# ESP8266-Thing-Dev.net
KiCad netlist of a schematic drawn in EAGLE
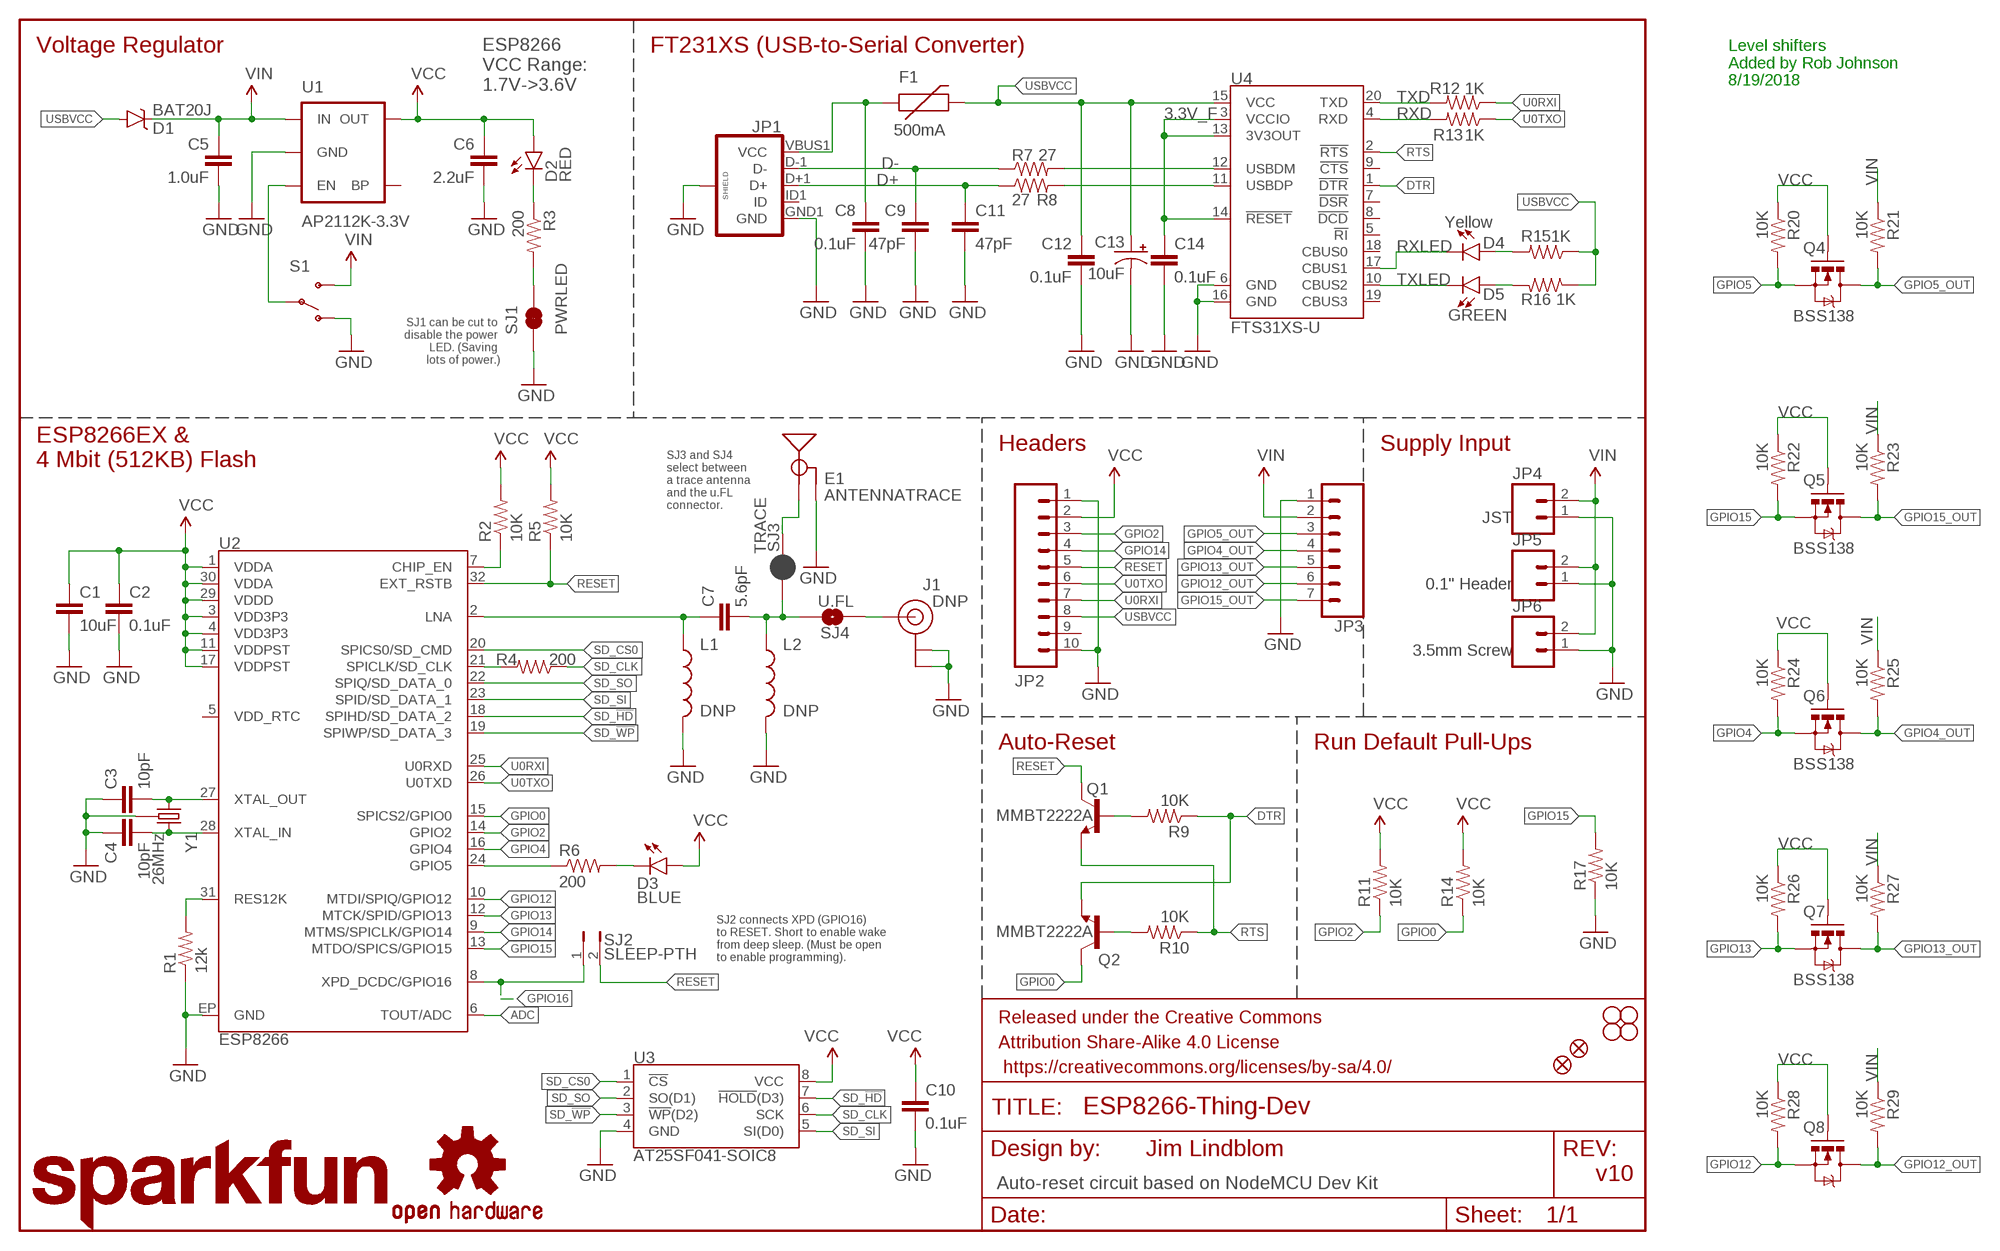
[diagram p0: schematic, sheet 1]

(export (version "E")
  (design (tool "Eeschema 10.0.6"))
  (components
    (comp (ref "C1")
      (value "10uF")
      (footprint "eagle-import:0603-CAP")
      (libsource (lib "eagle-import") (part "10UF-6.3V-20%(0603)"))
    )
    (comp (ref "C2")
      (value "0.1uF")
      (footprint "eagle-import:0603-CAP")
      (libsource (lib "eagle-import") (part "0.1UF-25V(+80/-20%)(0603)"))
    )
    (comp (ref "C3")
      (value "10pF")
      (footprint "eagle-import:0603-CAP")
      (libsource (lib "eagle-import") (part "10PF-50V-5%(0603)"))
    )
    (comp (ref "C4")
      (value "10pF")
      (footprint "eagle-import:0603-CAP")
      (libsource (lib "eagle-import") (part "10PF-50V-5%(0603)"))
    )
    (comp (ref "C5")
      (value "1.0uF")
      (footprint "eagle-import:0805")
      (libsource (lib "eagle-import") (part "1.0UF-25V-+80/-20(0805)"))
    )
    (comp (ref "C6")
      (value "2.2uF")
      (footprint "eagle-import:0603-CAP")
      (libsource (lib "eagle-import") (part "2.2UF-10V-20%(0603)"))
    )
    (comp (ref "C7")
      (value "5.6pF")
      (footprint "eagle-import:0603-CAP")
      (libsource (lib "eagle-import") (part "CAP0603-CAP"))
    )
    (comp (ref "C8")
      (value "0.1uF")
      (footprint "eagle-import:0603-CAP")
      (libsource (lib "eagle-import") (part "0.1UF-25V(+80/-20%)(0603)"))
    )
    (comp (ref "C9")
      (value "47pF")
      (footprint "eagle-import:0603-CAP")
      (libsource (lib "eagle-import") (part "47PF-50V-5%(0603)"))
    )
    (comp (ref "C10")
      (value "0.1uF")
      (footprint "eagle-import:0603-CAP")
      (libsource (lib "eagle-import") (part "0.1UF-25V(+80/-20%)(0603)"))
    )
    (comp (ref "C11")
      (value "47pF")
      (footprint "eagle-import:0603-CAP")
      (libsource (lib "eagle-import") (part "47PF-50V-5%(0603)"))
    )
    (comp (ref "C12")
      (value "0.1uF")
      (footprint "eagle-import:0603-CAP")
      (libsource (lib "eagle-import") (part "0.1UF-25V(+80/-20%)(0603)"))
    )
    (comp (ref "C13")
      (value "10uF")
      (footprint "eagle-import:EIA3216")
      (libsource (lib "eagle-import") (part "10UF-16V-10%(TANT)"))
    )
    (comp (ref "C14")
      (value "0.1uF")
      (footprint "eagle-import:0603-CAP")
      (libsource (lib "eagle-import") (part "0.1UF-25V(+80/-20%)(0603)"))
    )
    (comp (ref "D1")
      (value "BAT20J")
      (footprint "eagle-import:SOD-323")
      (libsource (lib "eagle-import") (part "DIODE-SCHOTTKY-BAT20J"))
    )
    (comp (ref "D2")
      (value "RED")
      (footprint "eagle-import:LED-0603")
      (libsource (lib "eagle-import") (part "LED-RED0603"))
    )
    (comp (ref "D3")
      (value "BLUE")
      (footprint "eagle-import:LED-0603")
      (libsource (lib "eagle-import") (part "LED-BLUE0603"))
    )
    (comp (ref "D4")
      (value "Yellow")
      (footprint "eagle-import:LED-0603")
      (libsource (lib "eagle-import") (part "LED-YELLOW0603"))
    )
    (comp (ref "D5")
      (value "GREEN")
      (footprint "eagle-import:LED-0603")
      (libsource (lib "eagle-import") (part "LED-GREEN0603"))
    )
    (comp (ref "E1")
      (value "ANTENNATRACE")
      (footprint "eagle-import:TRACE_ANTENNA_2.4GHZ_25.7MM")
      (libsource (lib "eagle-import") (part "ANTENNATRACE"))
    )
    (comp (ref "F1")
      (value "500mA")
      (footprint "eagle-import:PTC-1206")
      (libsource (lib "eagle-import") (part "PTCSMD"))
    )
    (comp (ref "FID1")
      (value "FIDUCIAL1X2")
      (footprint "eagle-import:FIDUCIAL-1X2")
      (libsource (lib "eagle-import") (part "FIDUCIAL1X2"))
    )
    (comp (ref "FID2")
      (value "FIDUCIAL1X2")
      (footprint "eagle-import:FIDUCIAL-1X2")
      (libsource (lib "eagle-import") (part "FIDUCIAL1X2"))
    )
    (comp (ref "FRAME1")
      (value "FRAME-LETTER")
      (footprint "eagle-import:CREATIVE_COMMONS")
      (libsource (lib "eagle-import") (part "FRAME-LETTER"))
    )
    (comp (ref "J1")
      (value "DNP")
      (footprint "eagle-import:U.FL")
      (libsource (lib "eagle-import") (part "U.FL"))
    )
    (comp (ref "JP1")
      (value "USB_MICROB_PLUGCONN-11752")
      (footprint "eagle-import:USB-B-MICRO-SMD_V03")
      (libsource (lib "eagle-import") (part "USB_MICROB_PLUGCONN-11752"))
    )
    (comp (ref "JP2")
      (value "M10NO_SILK_PTH_FEMALE")
      (footprint "eagle-import:1X10_NO_SILK")
      (libsource (lib "eagle-import") (part "M10NO_SILK_PTH_FEMALE"))
    )
    (comp (ref "JP3")
      (value "CONN_07NO_SILK")
      (footprint "eagle-import:1X07_NO_SILK")
      (libsource (lib "eagle-import") (part "CONN_07NO_SILK"))
    )
    (comp (ref "JP4")
      (value "M02JST-PTH-2")
      (footprint "eagle-import:JST-2-PTH")
      (libsource (lib "eagle-import") (part "M02JST-PTH-2"))
    )
    (comp (ref "JP5")
      (value "M021X02_NO_SILK")
      (footprint "eagle-import:1X02_NO_SILK")
      (libsource (lib "eagle-import") (part "M021X02_NO_SILK"))
    )
    (comp (ref "JP6")
      (value "M023.5MM-NO_SILK")
      (footprint "eagle-import:SCREWTERMINAL-3.5MM-2-NS")
      (libsource (lib "eagle-import") (part "M023.5MM-NO_SILK"))
    )
    (comp (ref "L1")
      (value "DNP")
      (footprint "eagle-import:0603")
      (libsource (lib "eagle-import") (part "INDUCTOR0603"))
    )
    (comp (ref "L2")
      (value "DNP")
      (footprint "eagle-import:0603")
      (libsource (lib "eagle-import") (part "INDUCTOR0603"))
    )
    (comp (ref "LOGO1")
      (value "SFE_LOGO_NAME.2_INCH")
      (footprint "eagle-import:SFE_LOGO_NAME_.2")
      (libsource (lib "eagle-import") (part "SFE_LOGO_NAME.2_INCH"))
    )
    (comp (ref "LOGO2")
      (value "OSHW-LOGOS")
      (footprint "eagle-import:OSHW-LOGO-S")
      (libsource (lib "eagle-import") (part "OSHW-LOGOS"))
    )
    (comp (ref "Q1")
      (value "MMBT2222A")
      (footprint "eagle-import:SOT23-3")
      (libsource (lib "eagle-import") (part "TRANSISTOR_NPNMMBT2222A"))
    )
    (comp (ref "Q2")
      (value "MMBT2222A")
      (footprint "eagle-import:SOT23-3")
      (libsource (lib "eagle-import") (part "TRANSISTOR_NPNMMBT2222A"))
    )
    (comp (ref "Q4")
      (value "BSS138")
      (footprint "eagle-import:SOT23-3")
      (libsource (lib "eagle-import") (part "MOSFET-NCHANNELSMD"))
    )
    (comp (ref "Q5")
      (value "BSS138")
      (footprint "eagle-import:SOT23-3")
      (libsource (lib "eagle-import") (part "MOSFET-NCHANNELSMD"))
    )
    (comp (ref "Q6")
      (value "BSS138")
      (footprint "eagle-import:SOT23-3")
      (libsource (lib "eagle-import") (part "MOSFET-NCHANNELSMD"))
    )
    (comp (ref "Q7")
      (value "BSS138")
      (footprint "eagle-import:SOT23-3")
      (libsource (lib "eagle-import") (part "MOSFET-NCHANNELSMD"))
    )
    (comp (ref "Q8")
      (value "BSS138")
      (footprint "eagle-import:SOT23-3")
      (libsource (lib "eagle-import") (part "MOSFET-NCHANNELSMD"))
    )
    (comp (ref "R1")
      (value "12k")
      (footprint "eagle-import:0603-RES")
      (libsource (lib "eagle-import") (part "12KOHM-1/10W-1%(0603)"))
    )
    (comp (ref "R2")
      (value "10K")
      (footprint "eagle-import:0603-RES")
      (libsource (lib "eagle-import") (part "10KOHM1/10W1%(0603)0603"))
    )
    (comp (ref "R3")
      (value "200")
      (footprint "eagle-import:0603-RES")
      (libsource (lib "eagle-import") (part "200OHM1/10W1%(0603)"))
    )
    (comp (ref "R4")
      (value "200")
      (footprint "eagle-import:0603-RES")
      (libsource (lib "eagle-import") (part "200OHM1/10W1%(0603)"))
    )
    (comp (ref "R5")
      (value "10K")
      (footprint "eagle-import:0603-RES")
      (libsource (lib "eagle-import") (part "10KOHM1/10W1%(0603)0603"))
    )
    (comp (ref "R6")
      (value "200")
      (footprint "eagle-import:0603-RES")
      (libsource (lib "eagle-import") (part "200OHM1/10W1%(0603)"))
    )
    (comp (ref "R7")
      (value "27")
      (footprint "eagle-import:0603-RES")
      (libsource (lib "eagle-import") (part "27OHM1/10W1%(0603)0603-RES"))
    )
    (comp (ref "R8")
      (value "27")
      (footprint "eagle-import:0603-RES")
      (libsource (lib "eagle-import") (part "27OHM1/10W1%(0603)0603-RES"))
    )
    (comp (ref "R9")
      (value "10K")
      (footprint "eagle-import:0603-RES")
      (libsource (lib "eagle-import") (part "10KOHM1/10W1%(0603)0603"))
    )
    (comp (ref "R10")
      (value "10K")
      (footprint "eagle-import:0603-RES")
      (libsource (lib "eagle-import") (part "10KOHM1/10W1%(0603)0603"))
    )
    (comp (ref "R11")
      (value "10K")
      (footprint "eagle-import:0603-RES")
      (libsource (lib "eagle-import") (part "10KOHM1/10W1%(0603)0603"))
    )
    (comp (ref "R12")
      (value "1K")
      (footprint "eagle-import:0603-RES")
      (libsource (lib "eagle-import") (part "1KOHM-1/10W-1%(0603)"))
    )
    (comp (ref "R13")
      (value "1K")
      (footprint "eagle-import:0603-RES")
      (libsource (lib "eagle-import") (part "1KOHM-1/10W-1%(0603)"))
    )
    (comp (ref "R14")
      (value "10K")
      (footprint "eagle-import:0603-RES")
      (libsource (lib "eagle-import") (part "10KOHM1/10W1%(0603)0603"))
    )
    (comp (ref "R15")
      (value "1K")
      (footprint "eagle-import:0603-RES")
      (libsource (lib "eagle-import") (part "1KOHM-1/10W-1%(0603)"))
    )
    (comp (ref "R16")
      (value "1K")
      (footprint "eagle-import:0603-RES")
      (libsource (lib "eagle-import") (part "1KOHM-1/10W-1%(0603)"))
    )
    (comp (ref "R17")
      (value "10K")
      (footprint "eagle-import:0603-RES")
      (libsource (lib "eagle-import") (part "10KOHM1/10W1%(0603)0603"))
    )
    (comp (ref "R20")
      (value "10K")
      (footprint "eagle-import:0603-RES")
      (libsource (lib "eagle-import") (part "RESISTOR0603-RES"))
    )
    (comp (ref "R21")
      (value "10K")
      (footprint "eagle-import:0603-RES")
      (libsource (lib "eagle-import") (part "RESISTOR0603-RES"))
    )
    (comp (ref "R22")
      (value "10K")
      (footprint "eagle-import:0603-RES")
      (libsource (lib "eagle-import") (part "RESISTOR0603-RES"))
    )
    (comp (ref "R23")
      (value "10K")
      (footprint "eagle-import:0603-RES")
      (libsource (lib "eagle-import") (part "RESISTOR0603-RES"))
    )
    (comp (ref "R24")
      (value "10K")
      (footprint "eagle-import:0603-RES")
      (libsource (lib "eagle-import") (part "RESISTOR0603-RES"))
    )
    (comp (ref "R25")
      (value "10K")
      (footprint "eagle-import:0603-RES")
      (libsource (lib "eagle-import") (part "RESISTOR0603-RES"))
    )
    (comp (ref "R26")
      (value "10K")
      (footprint "eagle-import:0603-RES")
      (libsource (lib "eagle-import") (part "RESISTOR0603-RES"))
    )
    (comp (ref "R27")
      (value "10K")
      (footprint "eagle-import:0603-RES")
      (libsource (lib "eagle-import") (part "RESISTOR0603-RES"))
    )
    (comp (ref "R28")
      (value "10K")
      (footprint "eagle-import:0603-RES")
      (libsource (lib "eagle-import") (part "RESISTOR0603-RES"))
    )
    (comp (ref "R29")
      (value "10K")
      (footprint "eagle-import:0603-RES")
      (libsource (lib "eagle-import") (part "RESISTOR0603-RES"))
    )
    (comp (ref "S1")
      (value "SWITCH-SPDT-SMD-A")
      (footprint "eagle-import:SWITCH-SPST-SMD-A")
      (libsource (lib "eagle-import") (part "SWITCH-SPDT-SMD-A"))
    )
    (comp (ref "SJ1")
      (value "PWRLED")
      (footprint "eagle-import:PAD-JUMPER-2-NC_BY_TRACE_YES_SILK")
      (libsource (lib "eagle-import") (part "JUMPER-PAD-2-NC_BY_TRACE"))
    )
    (comp (ref "SJ2")
      (value "SLEEP-PTH")
      (footprint "eagle-import:PTH-JUMPER-2-NO_NO_SILK")
      (libsource (lib "eagle-import") (part "JUMPER-PTH-2-NO"))
    )
    (comp (ref "SJ3")
      (value "TRACE")
      (footprint "eagle-import:PAD-JUMPER-2-NC_BY_PASTE_NO_SILK")
      (libsource (lib "eagle-import") (part "JUMPER-PAD-2-NC_BY_PASTENO-SILK"))
    )
    (comp (ref "SJ4")
      (value "U.FL")
      (footprint "eagle-import:PAD-JUMPER-2-NO_NO_SILK")
      (libsource (lib "eagle-import") (part "JUMPER-PAD-2-NO"))
    )
    (comp (ref "STANDOFF1")
      (value "STAND-OFF")
      (footprint "eagle-import:STAND-OFF")
      (libsource (lib "eagle-import") (part "STAND-OFF"))
    )
    (comp (ref "STANDOFF2")
      (value "STAND-OFF")
      (footprint "eagle-import:STAND-OFF")
      (libsource (lib "eagle-import") (part "STAND-OFF"))
    )
    (comp (ref "STANDOFF3")
      (value "STAND-OFF")
      (footprint "eagle-import:STAND-OFF")
      (libsource (lib "eagle-import") (part "STAND-OFF"))
    )
    (comp (ref "STANDOFF4")
      (value "STAND-OFF")
      (footprint "eagle-import:STAND-OFF")
      (libsource (lib "eagle-import") (part "STAND-OFF"))
    )
    (comp (ref "U1")
      (value "AP2112K-3.3V")
      (footprint "eagle-import:SOT23-5")
      (libsource (lib "eagle-import") (part "V_REG_LDOSMD"))
    )
    (comp (ref "U2")
      (value "ESP8266")
      (footprint "eagle-import:QFN32")
      (libsource (lib "eagle-import") (part "ESP8266"))
    )
    (comp (ref "U3")
      (value "AT25SF041-SOIC8")
      (footprint "eagle-import:SO08")
      (libsource (lib "eagle-import") (part "AT25SF041-SOIC8"))
    )
    (comp (ref "U4")
      (value "FTS31XS-U")
      (footprint "eagle-import:SSOP20_L")
      (libsource (lib "eagle-import") (part "FT231XS"))
    )
    (comp (ref "Y1")
      (value "26MHz")
      (footprint "eagle-import:CRYSTAL-SMD-3.2X2.5")
      (libsource (lib "eagle-import") (part "CRYSTAL-GROUNDED3.2X2.5"))
    )
  )
  (nets
    (net (code "1") (name "/3.3V_F") (class "Default")
      (node (ref "C14") (pin "1") (pinfunction "1_1") (pintype "passive"))
      (node (ref "U4") (pin "13") (pinfunction "3V3OUT_13") (pintype "bidirectional"))
      (node (ref "U4") (pin "14") (pinfunction "~{RESET}_14") (pintype "bidirectional"))
      (node (ref "U4") (pin "3") (pinfunction "VCCIO_3") (pintype "bidirectional"))
    )
    (net (code "2") (name "/D+") (class "Default")
      (node (ref "C11") (pin "1") (pinfunction "1_1") (pintype "passive"))
      (node (ref "JP1") (pin "D+1") (pinfunction "D+_D+1") (pintype "bidirectional"))
      (node (ref "R8") (pin "1") (pinfunction "1_1") (pintype "passive"))
    )
    (net (code "3") (name "/D-") (class "Default")
      (node (ref "C9") (pin "1") (pinfunction "1_1") (pintype "passive"))
      (node (ref "JP1") (pin "D-1") (pinfunction "D-_D-1") (pintype "bidirectional"))
      (node (ref "R7") (pin "1") (pinfunction "1_1") (pintype "passive"))
    )
    (net (code "4") (name "/RXD") (class "Default")
      (node (ref "R13") (pin "2") (pinfunction "2_2") (pintype "passive"))
      (node (ref "U4") (pin "4") (pinfunction "RXD_4") (pintype "bidirectional"))
    )
    (net (code "5") (name "/RXLED") (class "Default")
      (node (ref "D4") (pin "C") (pinfunction "C_C") (pintype "passive"))
      (node (ref "U4") (pin "17") (pinfunction "CBUS1_17") (pintype "bidirectional"))
    )
    (net (code "6") (name "/SD_~{HD}") (class "Default")
      (node (ref "U2") (pin "18") (pinfunction "SPIHD/SD_DATA_2_18") (pintype "bidirectional"))
      (node (ref "U3") (pin "7") (pinfunction "~{HOLD}(D3)_7") (pintype "bidirectional"))
    )
    (net (code "7") (name "/SD_~{WP}") (class "Default")
      (node (ref "U2") (pin "19") (pinfunction "SPIWP/SD_DATA_3_19") (pintype "bidirectional"))
      (node (ref "U3") (pin "3") (pinfunction "~{WP}(D2)_3") (pintype "bidirectional"))
    )
    (net (code "8") (name "/TXD") (class "Default")
      (node (ref "R12") (pin "2") (pinfunction "2_2") (pintype "passive"))
      (node (ref "U4") (pin "20") (pinfunction "TXD_20") (pintype "bidirectional"))
    )
    (net (code "9") (name "/TXLED") (class "Default")
      (node (ref "D5") (pin "C") (pinfunction "C_C") (pintype "passive"))
      (node (ref "U4") (pin "10") (pinfunction "CBUS2_10") (pintype "bidirectional"))
    )
    (net (code "10") (name "ADC") (class "Default")
      (node (ref "U2") (pin "6") (pinfunction "TOUT/ADC_6") (pintype "bidirectional"))
    )
    (net (code "11") (name "DTR") (class "Default")
      (node (ref "Q2") (pin "2") (pinfunction "E_2") (pintype "passive"))
      (node (ref "R9") (pin "1") (pinfunction "1_1") (pintype "passive"))
      (node (ref "U4") (pin "1") (pinfunction "~{DTR}_1") (pintype "bidirectional"))
    )
    (net (code "12") (name "GND") (class "Default")
      (node (ref "C1") (pin "2") (pinfunction "2_2") (pintype "passive"))
      (node (ref "C10") (pin "2") (pinfunction "2_2") (pintype "passive"))
      (node (ref "C11") (pin "2") (pinfunction "2_2") (pintype "passive"))
      (node (ref "C12") (pin "2") (pinfunction "2_2") (pintype "passive"))
      (node (ref "C13") (pin "C") (pinfunction "-_C") (pintype "passive"))
      (node (ref "C14") (pin "2") (pinfunction "2_2") (pintype "passive"))
      (node (ref "C2") (pin "2") (pinfunction "2_2") (pintype "passive"))
      (node (ref "C3") (pin "1") (pinfunction "1_1") (pintype "passive"))
      (node (ref "C4") (pin "1") (pinfunction "1_1") (pintype "passive"))
      (node (ref "C5") (pin "2") (pinfunction "2_2") (pintype "passive"))
      (node (ref "C6") (pin "2") (pinfunction "2_2") (pintype "passive"))
      (node (ref "C8") (pin "2") (pinfunction "2_2") (pintype "passive"))
      (node (ref "C9") (pin "2") (pinfunction "2_2") (pintype "passive"))
      (node (ref "E1") (pin "GND") (pinfunction "GND_GND") (pintype "bidirectional"))
      (node (ref "E1") (pin "GND2") (pinfunction "GND_GND2") (pintype "bidirectional"))
      (node (ref "J1") (pin "P$1") (pinfunction "GND_P$1") (pintype "bidirectional"))
      (node (ref "J1") (pin "P$2") (pinfunction "GND_P$2") (pintype "bidirectional"))
      (node (ref "JP1") (pin "GND1") (pinfunction "GND_GND1") (pintype "bidirectional"))
      (node (ref "JP1") (pin "SHIELD1") (pinfunction "SHIELD_SHIELD1") (pintype "bidirectional"))
      (node (ref "JP1") (pin "SHIELD2") (pinfunction "SHIELD_SHIELD2") (pintype "bidirectional"))
      (node (ref "JP1") (pin "SHIELD3") (pinfunction "SHIELD_SHIELD3") (pintype "bidirectional"))
      (node (ref "JP2") (pin "1") (pinfunction "1_1") (pintype "passive"))
      (node (ref "JP2") (pin "10") (pinfunction "10_10") (pintype "passive"))
      (node (ref "JP3") (pin "1") (pinfunction "1_1") (pintype "passive"))
      (node (ref "JP4") (pin "1") (pinfunction "1_1") (pintype "passive"))
      (node (ref "JP5") (pin "1") (pinfunction "1_1") (pintype "passive"))
      (node (ref "JP6") (pin "1") (pinfunction "1_1") (pintype "passive"))
      (node (ref "L1") (pin "2") (pinfunction "2_2") (pintype "passive"))
      (node (ref "L2") (pin "2") (pinfunction "2_2") (pintype "passive"))
      (node (ref "R1") (pin "1") (pinfunction "1_1") (pintype "passive"))
      (node (ref "R17") (pin "1") (pinfunction "1_1") (pintype "passive"))
      (node (ref "S1") (pin "1") (pinfunction "O_1") (pintype "passive"))
      (node (ref "SJ1") (pin "1") (pinfunction "1_1") (pintype "passive"))
      (node (ref "U1") (pin "2") (pinfunction "GND_2") (pintype "input"))
      (node (ref "U2") (pin "EP") (pinfunction "GND_EP") (pintype "bidirectional"))
      (node (ref "U3") (pin "4") (pinfunction "GND_4") (pintype "bidirectional"))
      (node (ref "U4") (pin "16") (pinfunction "GND_16") (pintype "bidirectional"))
      (node (ref "U4") (pin "6") (pinfunction "GND_6") (pintype "bidirectional"))
      (node (ref "Y1") (pin "2") (pinfunction "GND_2") (pintype "passive"))
      (node (ref "Y1") (pin "4") (pinfunction "GND_4") (pintype "passive"))
    )
    (net (code "13") (name "GPIO0") (class "Default")
      (node (ref "Q2") (pin "3") (pinfunction "C_3") (pintype "passive"))
      (node (ref "R14") (pin "1") (pinfunction "1_1") (pintype "passive"))
      (node (ref "U2") (pin "15") (pinfunction "SPICS2/GPIO0_15") (pintype "bidirectional"))
    )
    (net (code "14") (name "GPIO2") (class "Default")
      (node (ref "JP2") (pin "3") (pinfunction "3_3") (pintype "passive"))
      (node (ref "R11") (pin "1") (pinfunction "1_1") (pintype "passive"))
      (node (ref "U2") (pin "14") (pinfunction "GPIO2_14") (pintype "bidirectional"))
    )
    (net (code "15") (name "GPIO4") (class "Default")
      (node (ref "Q6") (pin "2") (pinfunction "S_2") (pintype "passive"))
      (node (ref "R24") (pin "2") (pinfunction "2_2") (pintype "passive"))
      (node (ref "U2") (pin "16") (pinfunction "GPIO4_16") (pintype "bidirectional"))
    )
    (net (code "16") (name "GPIO4_OUT") (class "Default")
      (node (ref "JP3") (pin "4") (pinfunction "4_4") (pintype "passive"))
      (node (ref "Q6") (pin "3") (pinfunction "D_3") (pintype "passive"))
      (node (ref "R25") (pin "2") (pinfunction "2_2") (pintype "passive"))
    )
    (net (code "17") (name "GPIO5") (class "Default")
      (node (ref "Q4") (pin "2") (pinfunction "S_2") (pintype "passive"))
      (node (ref "R20") (pin "2") (pinfunction "2_2") (pintype "passive"))
      (node (ref "R6") (pin "1") (pinfunction "1_1") (pintype "passive"))
      (node (ref "U2") (pin "24") (pinfunction "GPIO5_24") (pintype "bidirectional"))
    )
    (net (code "18") (name "GPIO5_OUT") (class "Default")
      (node (ref "JP3") (pin "3") (pinfunction "3_3") (pintype "passive"))
      (node (ref "Q4") (pin "3") (pinfunction "D_3") (pintype "passive"))
      (node (ref "R21") (pin "2") (pinfunction "2_2") (pintype "passive"))
    )
    (net (code "19") (name "GPIO12") (class "Default")
      (node (ref "Q8") (pin "2") (pinfunction "S_2") (pintype "passive"))
      (node (ref "R28") (pin "2") (pinfunction "2_2") (pintype "passive"))
      (node (ref "U2") (pin "10") (pinfunction "MTDI/SPIQ/GPIO12_10") (pintype "bidirectional"))
    )
    (net (code "20") (name "GPIO12_OUT") (class "Default")
      (node (ref "JP3") (pin "6") (pinfunction "6_6") (pintype "passive"))
      (node (ref "Q8") (pin "3") (pinfunction "D_3") (pintype "passive"))
      (node (ref "R29") (pin "2") (pinfunction "2_2") (pintype "passive"))
    )
    (net (code "21") (name "GPIO13") (class "Default")
      (node (ref "Q7") (pin "2") (pinfunction "S_2") (pintype "passive"))
      (node (ref "R26") (pin "2") (pinfunction "2_2") (pintype "passive"))
      (node (ref "U2") (pin "12") (pinfunction "MTCK/SPID/GPIO13_12") (pintype "bidirectional"))
    )
    (net (code "22") (name "GPIO13_OUT") (class "Default")
      (node (ref "JP3") (pin "5") (pinfunction "5_5") (pintype "passive"))
      (node (ref "Q7") (pin "3") (pinfunction "D_3") (pintype "passive"))
      (node (ref "R27") (pin "2") (pinfunction "2_2") (pintype "passive"))
    )
    (net (code "23") (name "GPIO14") (class "Default")
      (node (ref "JP2") (pin "4") (pinfunction "4_4") (pintype "passive"))
      (node (ref "U2") (pin "9") (pinfunction "MTMS/SPICLK/GPIO14_9") (pintype "bidirectional"))
    )
    (net (code "24") (name "GPIO15") (class "Default")
      (node (ref "Q5") (pin "2") (pinfunction "S_2") (pintype "passive"))
      (node (ref "R17") (pin "2") (pinfunction "2_2") (pintype "passive"))
      (node (ref "R22") (pin "2") (pinfunction "2_2") (pintype "passive"))
      (node (ref "U2") (pin "13") (pinfunction "MTDO/SPICS/GPIO15_13") (pintype "bidirectional"))
    )
    (net (code "25") (name "GPIO15_OUT") (class "Default")
      (node (ref "JP3") (pin "7") (pinfunction "7_7") (pintype "passive"))
      (node (ref "Q5") (pin "3") (pinfunction "D_3") (pintype "passive"))
      (node (ref "R23") (pin "2") (pinfunction "2_2") (pintype "passive"))
    )
    (net (code "26") (name "GPIO16") (class "Default")
      (node (ref "SJ2") (pin "1") (pinfunction "1_1") (pintype "passive"))
      (node (ref "U2") (pin "8") (pinfunction "XPD_DCDC/GPIO16_8") (pintype "bidirectional"))
    )
    (net (code "27") (name "Net-(C7-Pad2)") (class "Default")
      (node (ref "C7") (pin "2") (pinfunction "2_2") (pintype "passive"))
      (node (ref "L2") (pin "1") (pinfunction "1_1") (pintype "passive"))
      (node (ref "SJ3") (pin "1") (pinfunction "1_1") (pintype "passive"))
      (node (ref "SJ4") (pin "2") (pinfunction "2_2") (pintype "passive"))
    )
    (net (code "28") (name "Net-(D2-PadC)") (class "Default")
      (node (ref "D2") (pin "C") (pinfunction "C_C") (pintype "passive"))
      (node (ref "R3") (pin "1") (pinfunction "1_1") (pintype "passive"))
    )
    (net (code "29") (name "Net-(D3-PadC)") (class "Default")
      (node (ref "D3") (pin "C") (pinfunction "C_C") (pintype "passive"))
      (node (ref "R6") (pin "2") (pinfunction "2_2") (pintype "passive"))
    )
    (net (code "30") (name "Net-(D4-PadA)") (class "Default")
      (node (ref "D4") (pin "A") (pinfunction "A_A") (pintype "passive"))
      (node (ref "R15") (pin "2") (pinfunction "2_2") (pintype "passive"))
    )
    (net (code "31") (name "Net-(D5-PadA)") (class "Default")
      (node (ref "D5") (pin "A") (pinfunction "A_A") (pintype "passive"))
      (node (ref "R16") (pin "2") (pinfunction "2_2") (pintype "passive"))
    )
    (net (code "32") (name "Net-(E1-SIGNAL)") (class "Default")
      (node (ref "E1") (pin "ANT") (pinfunction "SIGNAL_ANT") (pintype "bidirectional"))
      (node (ref "SJ3") (pin "2") (pinfunction "2_2") (pintype "passive"))
    )
    (net (code "33") (name "Net-(J1-SIGNAL)") (class "Default")
      (node (ref "J1") (pin "P$3") (pinfunction "SIGNAL_P$3") (pintype "bidirectional"))
      (node (ref "SJ4") (pin "1") (pinfunction "1_1") (pintype "passive"))
    )
    (net (code "34") (name "Net-(JP1-VCC)") (class "Default")
      (node (ref "C8") (pin "1") (pinfunction "1_1") (pintype "passive"))
      (node (ref "F1") (pin "1") (pinfunction "1_1") (pintype "bidirectional"))
      (node (ref "JP1") (pin "VBUS1") (pinfunction "VCC_VBUS1") (pintype "bidirectional"))
    )
    (net (code "35") (name "Net-(Q1-B)") (class "Default")
      (node (ref "Q1") (pin "1") (pinfunction "B_1") (pintype "passive"))
      (node (ref "R9") (pin "2") (pinfunction "2_2") (pintype "passive"))
    )
    (net (code "36") (name "Net-(Q2-B)") (class "Default")
      (node (ref "Q2") (pin "1") (pinfunction "B_1") (pintype "passive"))
      (node (ref "R10") (pin "2") (pinfunction "2_2") (pintype "passive"))
    )
    (net (code "37") (name "Net-(R3-Pad2)") (class "Default")
      (node (ref "R3") (pin "2") (pinfunction "2_2") (pintype "passive"))
      (node (ref "SJ1") (pin "2") (pinfunction "2_2") (pintype "passive"))
    )
    (net (code "38") (name "Net-(S1-P)") (class "Default")
      (node (ref "S1") (pin "2") (pinfunction "P_2") (pintype "passive"))
      (node (ref "U1") (pin "3") (pinfunction "EN_3") (pintype "input"))
    )
    (net (code "39") (name "Net-(U2-CHIP_EN)") (class "Default")
      (node (ref "R2") (pin "1") (pinfunction "1_1") (pintype "passive"))
      (node (ref "U2") (pin "7") (pinfunction "CHIP_EN_7") (pintype "bidirectional"))
    )
    (net (code "40") (name "Net-(U2-LNA)") (class "Default")
      (node (ref "C7") (pin "1") (pinfunction "1_1") (pintype "passive"))
      (node (ref "L1") (pin "1") (pinfunction "1_1") (pintype "passive"))
      (node (ref "U2") (pin "2") (pinfunction "LNA_2") (pintype "bidirectional"))
    )
    (net (code "41") (name "Net-(U2-RES12K)") (class "Default")
      (node (ref "R1") (pin "2") (pinfunction "2_2") (pintype "passive"))
      (node (ref "U2") (pin "31") (pinfunction "RES12K_31") (pintype "bidirectional"))
    )
    (net (code "42") (name "Net-(U2-SPICLK{slash}SD_CLK)") (class "Default")
      (node (ref "R4") (pin "2") (pinfunction "2_2") (pintype "passive"))
      (node (ref "U2") (pin "21") (pinfunction "SPICLK/SD_CLK_21") (pintype "bidirectional"))
    )
    (net (code "43") (name "Net-(U2-XTAL_IN)") (class "Default")
      (node (ref "C4") (pin "2") (pinfunction "2_2") (pintype "passive"))
      (node (ref "U2") (pin "28") (pinfunction "XTAL_IN_28") (pintype "bidirectional"))
      (node (ref "Y1") (pin "3") (pinfunction "2_3") (pintype "passive"))
    )
    (net (code "44") (name "Net-(U2-XTAL_OUT)") (class "Default")
      (node (ref "C3") (pin "2") (pinfunction "2_2") (pintype "passive"))
      (node (ref "U2") (pin "27") (pinfunction "XTAL_OUT_27") (pintype "bidirectional"))
      (node (ref "Y1") (pin "1") (pinfunction "1_1") (pintype "passive"))
    )
    (net (code "45") (name "Net-(U4-USBDM)") (class "Default")
      (node (ref "R7") (pin "2") (pinfunction "2_2") (pintype "passive"))
      (node (ref "U4") (pin "12") (pinfunction "USBDM_12") (pintype "bidirectional"))
    )
    (net (code "46") (name "Net-(U4-USBDP)") (class "Default")
      (node (ref "R8") (pin "2") (pinfunction "2_2") (pintype "passive"))
      (node (ref "U4") (pin "11") (pinfunction "USBDP_11") (pintype "bidirectional"))
    )
    (net (code "47") (name "RESET") (class "Default")
      (node (ref "JP2") (pin "5") (pinfunction "5_5") (pintype "passive"))
      (node (ref "Q1") (pin "3") (pinfunction "C_3") (pintype "passive"))
      (node (ref "R5") (pin "1") (pinfunction "1_1") (pintype "passive"))
      (node (ref "SJ2") (pin "2") (pinfunction "2_2") (pintype "passive"))
      (node (ref "U2") (pin "32") (pinfunction "EXT_RSTB_32") (pintype "bidirectional"))
    )
    (net (code "48") (name "RTS") (class "Default")
      (node (ref "Q1") (pin "2") (pinfunction "E_2") (pintype "passive"))
      (node (ref "R10") (pin "1") (pinfunction "1_1") (pintype "passive"))
      (node (ref "U4") (pin "2") (pinfunction "~{RTS}_2") (pintype "bidirectional"))
    )
    (net (code "49") (name "SD_CLK") (class "Default")
      (node (ref "R4") (pin "1") (pinfunction "1_1") (pintype "passive"))
      (node (ref "U3") (pin "6") (pinfunction "SCK_6") (pintype "bidirectional"))
    )
    (net (code "50") (name "SD_CS0") (class "Default")
      (node (ref "U2") (pin "20") (pinfunction "SPICS0/SD_CMD_20") (pintype "bidirectional"))
      (node (ref "U3") (pin "1") (pinfunction "~{CS}_1") (pintype "bidirectional"))
    )
    (net (code "51") (name "SD_SI") (class "Default")
      (node (ref "U2") (pin "23") (pinfunction "SPID/SD_DATA_1_23") (pintype "bidirectional"))
      (node (ref "U3") (pin "5") (pinfunction "SI(D0)_5") (pintype "bidirectional"))
    )
    (net (code "52") (name "SD_SO") (class "Default")
      (node (ref "U2") (pin "22") (pinfunction "SPIQ/SD_DATA_0_22") (pintype "bidirectional"))
      (node (ref "U3") (pin "2") (pinfunction "SO(D1)_2") (pintype "bidirectional"))
    )
    (net (code "53") (name "U0RXI") (class "Default")
      (node (ref "JP2") (pin "7") (pinfunction "7_7") (pintype "passive"))
      (node (ref "R12") (pin "1") (pinfunction "1_1") (pintype "passive"))
      (node (ref "U2") (pin "25") (pinfunction "U0RXD_25") (pintype "bidirectional"))
    )
    (net (code "54") (name "U0TXO") (class "Default")
      (node (ref "JP2") (pin "6") (pinfunction "6_6") (pintype "passive"))
      (node (ref "R13") (pin "1") (pinfunction "1_1") (pintype "passive"))
      (node (ref "U2") (pin "26") (pinfunction "U0TXD_26") (pintype "bidirectional"))
    )
    (net (code "55") (name "USBVCC") (class "Default")
      (node (ref "C12") (pin "1") (pinfunction "1_1") (pintype "passive"))
      (node (ref "C13") (pin "A") (pinfunction "+_A") (pintype "passive"))
      (node (ref "D1") (pin "A") (pinfunction "A_A") (pintype "passive"))
      (node (ref "F1") (pin "2") (pinfunction "2_2") (pintype "bidirectional"))
      (node (ref "JP2") (pin "8") (pinfunction "8_8") (pintype "passive"))
      (node (ref "R15") (pin "1") (pinfunction "1_1") (pintype "passive"))
      (node (ref "R16") (pin "1") (pinfunction "1_1") (pintype "passive"))
      (node (ref "U4") (pin "15") (pinfunction "VCC_15") (pintype "bidirectional"))
    )
    (net (code "56") (name "VCC") (class "Default")
      (node (ref "C1") (pin "1") (pinfunction "1_1") (pintype "passive"))
      (node (ref "C10") (pin "1") (pinfunction "1_1") (pintype "passive"))
      (node (ref "C2") (pin "1") (pinfunction "1_1") (pintype "passive"))
      (node (ref "C6") (pin "1") (pinfunction "1_1") (pintype "passive"))
      (node (ref "D2") (pin "A") (pinfunction "A_A") (pintype "passive"))
      (node (ref "D3") (pin "A") (pinfunction "A_A") (pintype "passive"))
      (node (ref "JP2") (pin "2") (pinfunction "2_2") (pintype "passive"))
      (node (ref "Q4") (pin "1") (pinfunction "G_1") (pintype "passive"))
      (node (ref "Q5") (pin "1") (pinfunction "G_1") (pintype "passive"))
      (node (ref "Q6") (pin "1") (pinfunction "G_1") (pintype "passive"))
      (node (ref "Q7") (pin "1") (pinfunction "G_1") (pintype "passive"))
      (node (ref "Q8") (pin "1") (pinfunction "G_1") (pintype "passive"))
      (node (ref "R11") (pin "2") (pinfunction "2_2") (pintype "passive"))
      (node (ref "R14") (pin "2") (pinfunction "2_2") (pintype "passive"))
      (node (ref "R2") (pin "2") (pinfunction "2_2") (pintype "passive"))
      (node (ref "R20") (pin "1") (pinfunction "1_1") (pintype "passive"))
      (node (ref "R22") (pin "1") (pinfunction "1_1") (pintype "passive"))
      (node (ref "R24") (pin "1") (pinfunction "1_1") (pintype "passive"))
      (node (ref "R26") (pin "1") (pinfunction "1_1") (pintype "passive"))
      (node (ref "R28") (pin "1") (pinfunction "1_1") (pintype "passive"))
      (node (ref "R5") (pin "2") (pinfunction "2_2") (pintype "passive"))
      (node (ref "U1") (pin "5") (pinfunction "OUT_5") (pintype "passive"))
      (node (ref "U2") (pin "1") (pinfunction "VDDA_1") (pintype "bidirectional"))
      (node (ref "U2") (pin "11") (pinfunction "VDDPST_11") (pintype "bidirectional"))
      (node (ref "U2") (pin "17") (pinfunction "VDDPST_17") (pintype "bidirectional"))
      (node (ref "U2") (pin "29") (pinfunction "VDDD_29") (pintype "bidirectional"))
      (node (ref "U2") (pin "3") (pinfunction "VDD3P3_3") (pintype "bidirectional"))
      (node (ref "U2") (pin "30") (pinfunction "VDDA_30") (pintype "bidirectional"))
      (node (ref "U2") (pin "4") (pinfunction "VDD3P3_4") (pintype "bidirectional"))
      (node (ref "U3") (pin "8") (pinfunction "VCC_8") (pintype "bidirectional"))
    )
    (net (code "57") (name "VIN") (class "Default")
      (node (ref "C5") (pin "1") (pinfunction "1_1") (pintype "passive"))
      (node (ref "D1") (pin "C") (pinfunction "C_C") (pintype "passive"))
      (node (ref "JP3") (pin "2") (pinfunction "2_2") (pintype "passive"))
      (node (ref "JP4") (pin "2") (pinfunction "2_2") (pintype "passive"))
      (node (ref "JP5") (pin "2") (pinfunction "2_2") (pintype "passive"))
      (node (ref "JP6") (pin "2") (pinfunction "2_2") (pintype "passive"))
      (node (ref "R21") (pin "1") (pinfunction "1_1") (pintype "passive"))
      (node (ref "R23") (pin "1") (pinfunction "1_1") (pintype "passive"))
      (node (ref "R25") (pin "1") (pinfunction "1_1") (pintype "passive"))
      (node (ref "R27") (pin "1") (pinfunction "1_1") (pintype "passive"))
      (node (ref "R29") (pin "1") (pinfunction "1_1") (pintype "passive"))
      (node (ref "S1") (pin "3") (pinfunction "S_3") (pintype "passive"))
      (node (ref "U1") (pin "1") (pinfunction "IN_1") (pintype "input"))
    )
    (net (code "58") (name "unconnected-(JP1-ID-PadID1)") (class "Default")
      (node (ref "JP1") (pin "ID1") (pinfunction "ID_ID1") (pintype "bidirectional"))
    )
    (net (code "59") (name "unconnected-(JP2-Pad9)") (class "Default")
      (node (ref "JP2") (pin "9") (pinfunction "9_9") (pintype "passive"))
    )
    (net (code "60") (name "unconnected-(U1-BP-Pad4)") (class "Default")
      (node (ref "U1") (pin "4") (pinfunction "BP_4") (pintype "input"))
    )
    (net (code "61") (name "unconnected-(U2-VDD_RTC-Pad5)") (class "Default")
      (node (ref "U2") (pin "5") (pinfunction "VDD_RTC_5") (pintype "bidirectional"))
    )
    (net (code "62") (name "unconnected-(U4-CBUS0-Pad18)") (class "Default")
      (node (ref "U4") (pin "18") (pinfunction "CBUS0_18") (pintype "bidirectional"))
    )
    (net (code "63") (name "unconnected-(U4-CBUS3-Pad19)") (class "Default")
      (node (ref "U4") (pin "19") (pinfunction "CBUS3_19") (pintype "bidirectional"))
    )
    (net (code "64") (name "unconnected-(U4-~{CTS}-Pad9)") (class "Default")
      (node (ref "U4") (pin "9") (pinfunction "~{CTS}_9") (pintype "bidirectional"))
    )
    (net (code "65") (name "unconnected-(U4-~{DCD}-Pad8)") (class "Default")
      (node (ref "U4") (pin "8") (pinfunction "~{DCD}_8") (pintype "bidirectional"))
    )
    (net (code "66") (name "unconnected-(U4-~{DSR}-Pad7)") (class "Default")
      (node (ref "U4") (pin "7") (pinfunction "~{DSR}_7") (pintype "bidirectional"))
    )
    (net (code "67") (name "unconnected-(U4-~{RI}-Pad5)") (class "Default")
      (node (ref "U4") (pin "5") (pinfunction "~{RI}_5") (pintype "bidirectional"))
    )
  )
)
